# SparkFun_Analog_MEMS_Microphone_Breakout.net
KiCad netlist of a schematic drawn in EAGLE
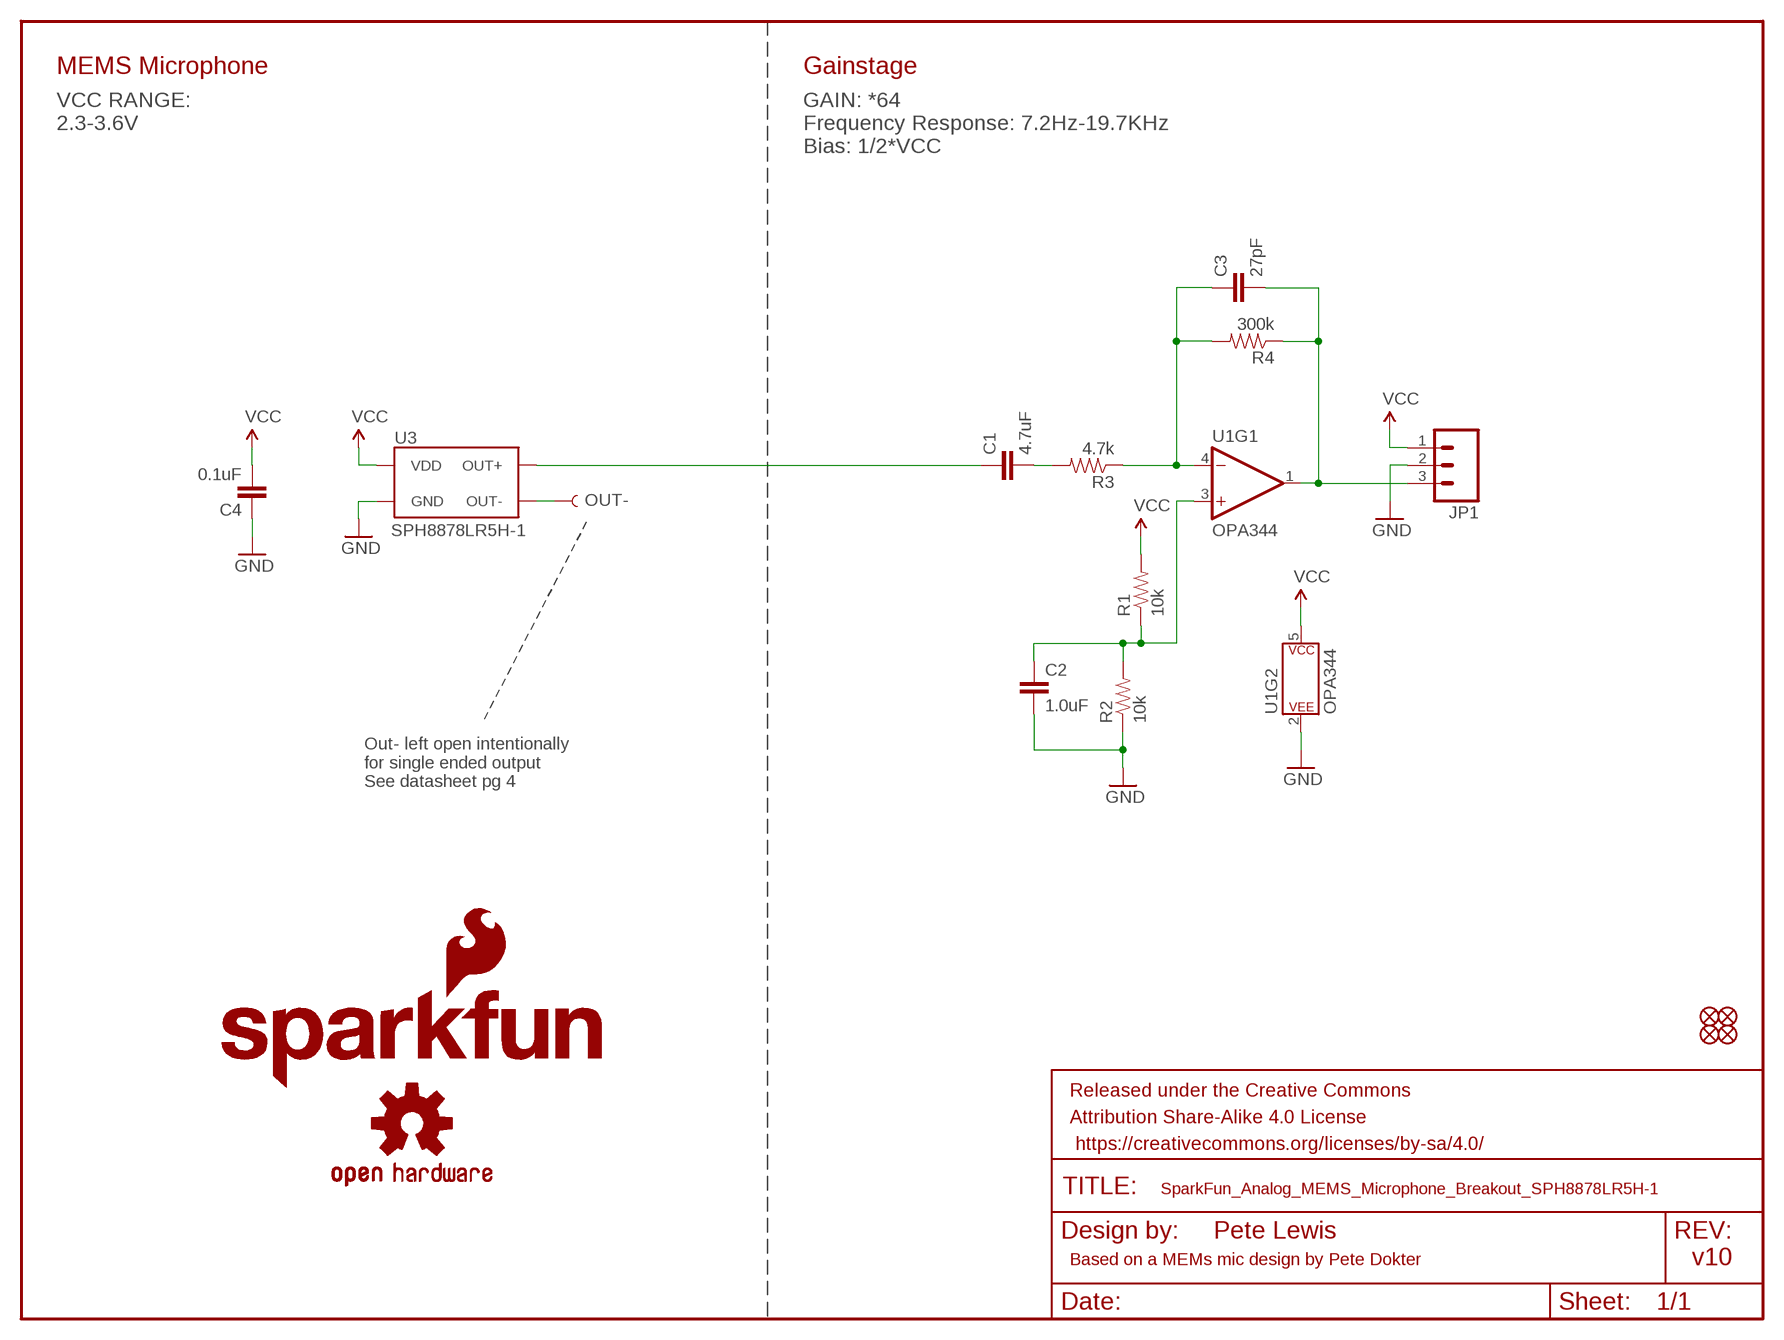
[diagram p0: schematic, sheet 1]

(export (version "E")
  (design (tool "Eeschema 10.0.6"))
  (components
    (comp (ref "C1")
      (value "4.7uF")
      (footprint "eagle-import:0603")
      (libsource (lib "eagle-import") (part "4.7UF-0603-6.3V-(10%)"))
    )
    (comp (ref "C2")
      (value "1.0uF")
      (footprint "eagle-import:0603")
      (libsource (lib "eagle-import") (part "1.0UF-0603-16V-10%"))
    )
    (comp (ref "C3")
      (value "27pF")
      (footprint "eagle-import:0603")
      (libsource (lib "eagle-import") (part "27PF-0603-50V-5%"))
    )
    (comp (ref "C4")
      (value "0.1uF")
      (footprint "eagle-import:0603")
      (libsource (lib "eagle-import") (part "0.1UF-0603-25V-(+80/-20%)"))
    )
    (comp (ref "FD1")
      (value "FIDUCIALUFIDUCIAL")
      (footprint "eagle-import:FIDUCIAL-MICRO")
      (libsource (lib "eagle-import") (part "FIDUCIALUFIDUCIAL"))
    )
    (comp (ref "FD2")
      (value "FIDUCIALUFIDUCIAL")
      (footprint "eagle-import:FIDUCIAL-MICRO")
      (libsource (lib "eagle-import") (part "FIDUCIALUFIDUCIAL"))
    )
    (comp (ref "FD3")
      (value "FIDUCIALUFIDUCIAL")
      (footprint "eagle-import:FIDUCIAL-MICRO")
      (libsource (lib "eagle-import") (part "FIDUCIALUFIDUCIAL"))
    )
    (comp (ref "FD4")
      (value "FIDUCIALUFIDUCIAL")
      (footprint "eagle-import:FIDUCIAL-MICRO")
      (libsource (lib "eagle-import") (part "FIDUCIALUFIDUCIAL"))
    )
    (comp (ref "FRAME2")
      (value "FRAME-LETTER")
      (footprint "eagle-import:CREATIVE_COMMONS")
      (libsource (lib "eagle-import") (part "FRAME-LETTER"))
    )
    (comp (ref "JP1")
      (value "CONN_031X03_NO_SILK")
      (footprint "eagle-import:1X03_NO_SILK")
      (libsource (lib "eagle-import") (part "CONN_031X03_NO_SILK"))
    )
    (comp (ref "LOGO1")
      (value "SFE_LOGO_FLAME.1_INCH")
      (footprint "eagle-import:SFE_LOGO_FLAME_.1")
      (libsource (lib "eagle-import") (part "SFE_LOGO_FLAME.1_INCH"))
    )
    (comp (ref "LOGO2")
      (value "OSHW-LOGOMINI")
      (footprint "eagle-import:OSHW-LOGO-MINI")
      (libsource (lib "eagle-import") (part "OSHW-LOGOMINI"))
    )
    (comp (ref "OUT-")
      (value "TEST-POINTTP_15TH_THRU")
      (footprint "eagle-import:TP_15TH")
      (libsource (lib "eagle-import") (part "TEST-POINTTP_15TH_THRU"))
    )
    (comp (ref "R1")
      (value "10k")
      (footprint "eagle-import:0603")
      (libsource (lib "eagle-import") (part "10KOHM-0603-1/10W-1%"))
    )
    (comp (ref "R2")
      (value "10k")
      (footprint "eagle-import:0603")
      (libsource (lib "eagle-import") (part "10KOHM-0603-1/10W-1%"))
    )
    (comp (ref "R3")
      (value "4.7k")
      (footprint "eagle-import:0603")
      (libsource (lib "eagle-import") (part "4.7KOHM-0603-1/10W-1%"))
    )
    (comp (ref "R4")
      (value "300k")
      (footprint "eagle-import:0603")
      (libsource (lib "eagle-import") (part "300KOHM-0603-1/10W-1%"))
    )
    (comp (ref "U1")
      (value "OPA344")
      (footprint "eagle-import:SOT23-5")
      (libsource (lib "eagle-import") (part "OPA344"))
    )
    (comp (ref "U3")
      (value "SPH8878LR5H-1")
      (footprint "eagle-import:SPH8878LR5H-1")
      (libsource (lib "eagle-import") (part "SPH8878LR5H-1"))
    )
  )
  (nets
    (net (code "1") (name "GND") (class "Default")
      (node (ref "C2") (pin "2") (pinfunction "2_2") (pintype "passive"))
      (node (ref "C4") (pin "1") (pinfunction "1_1") (pintype "passive"))
      (node (ref "JP1") (pin "2") (pinfunction "2_2") (pintype "passive"))
      (node (ref "R2") (pin "1") (pinfunction "1_1") (pintype "passive"))
      (node (ref "U1") (pin "2") (pinfunction "P$V-_2") (pintype "bidirectional"))
      (node (ref "U3") (pin "2") (pinfunction "GND_2") (pintype "bidirectional"))
      (node (ref "U3") (pin "3") (pinfunction "GND_3") (pintype "bidirectional"))
      (node (ref "U3") (pin "4") (pinfunction "GND_4") (pintype "bidirectional"))
    )
    (net (code "2") (name "Net-(C1-Pad2)") (class "Default")
      (node (ref "C1") (pin "2") (pinfunction "2_2") (pintype "passive"))
      (node (ref "R3") (pin "2") (pinfunction "2_2") (pintype "passive"))
    )
    (net (code "3") (name "Net-(U1A-+IN)") (class "Default")
      (node (ref "C2") (pin "1") (pinfunction "1_1") (pintype "passive"))
      (node (ref "R1") (pin "1") (pinfunction "1_1") (pintype "passive"))
      (node (ref "R2") (pin "2") (pinfunction "2_2") (pintype "passive"))
      (node (ref "U1") (pin "3") (pinfunction "+IN_3") (pintype "input"))
    )
    (net (code "4") (name "Net-(U1A--IN)") (class "Default")
      (node (ref "C3") (pin "1") (pinfunction "1_1") (pintype "passive"))
      (node (ref "R3") (pin "1") (pinfunction "1_1") (pintype "passive"))
      (node (ref "R4") (pin "2") (pinfunction "2_2") (pintype "passive"))
      (node (ref "U1") (pin "4") (pinfunction "-IN_4") (pintype "input"))
    )
    (net (code "5") (name "Net-(U1A-OUT)") (class "Default")
      (node (ref "C3") (pin "2") (pinfunction "2_2") (pintype "passive"))
      (node (ref "JP1") (pin "3") (pinfunction "3_3") (pintype "passive"))
      (node (ref "R4") (pin "1") (pinfunction "1_1") (pintype "passive"))
      (node (ref "U1") (pin "1") (pinfunction "OUT_1") (pintype "output"))
    )
    (net (code "6") (name "Net-(U3-OUT+)") (class "Default")
      (node (ref "C1") (pin "1") (pinfunction "1_1") (pintype "passive"))
      (node (ref "U3") (pin "1") (pinfunction "OUT+_1") (pintype "bidirectional"))
    )
    (net (code "7") (name "Net-(U3-OUT-)") (class "Default")
      (node (ref "OUT-") (pin "1") (pinfunction "1_1") (pintype "bidirectional"))
      (node (ref "U3") (pin "6") (pinfunction "OUT-_6") (pintype "bidirectional"))
    )
    (net (code "8") (name "VCC") (class "Default")
      (node (ref "C4") (pin "2") (pinfunction "2_2") (pintype "passive"))
      (node (ref "JP1") (pin "1") (pinfunction "1_1") (pintype "passive"))
      (node (ref "R1") (pin "2") (pinfunction "2_2") (pintype "passive"))
      (node (ref "U1") (pin "5") (pinfunction "P$V+_5") (pintype "bidirectional"))
      (node (ref "U3") (pin "5") (pinfunction "VDD_5") (pintype "bidirectional"))
    )
  )
)
